# SpaceFleaEPS.net
KiCad netlist of a schematic drawn in EAGLE
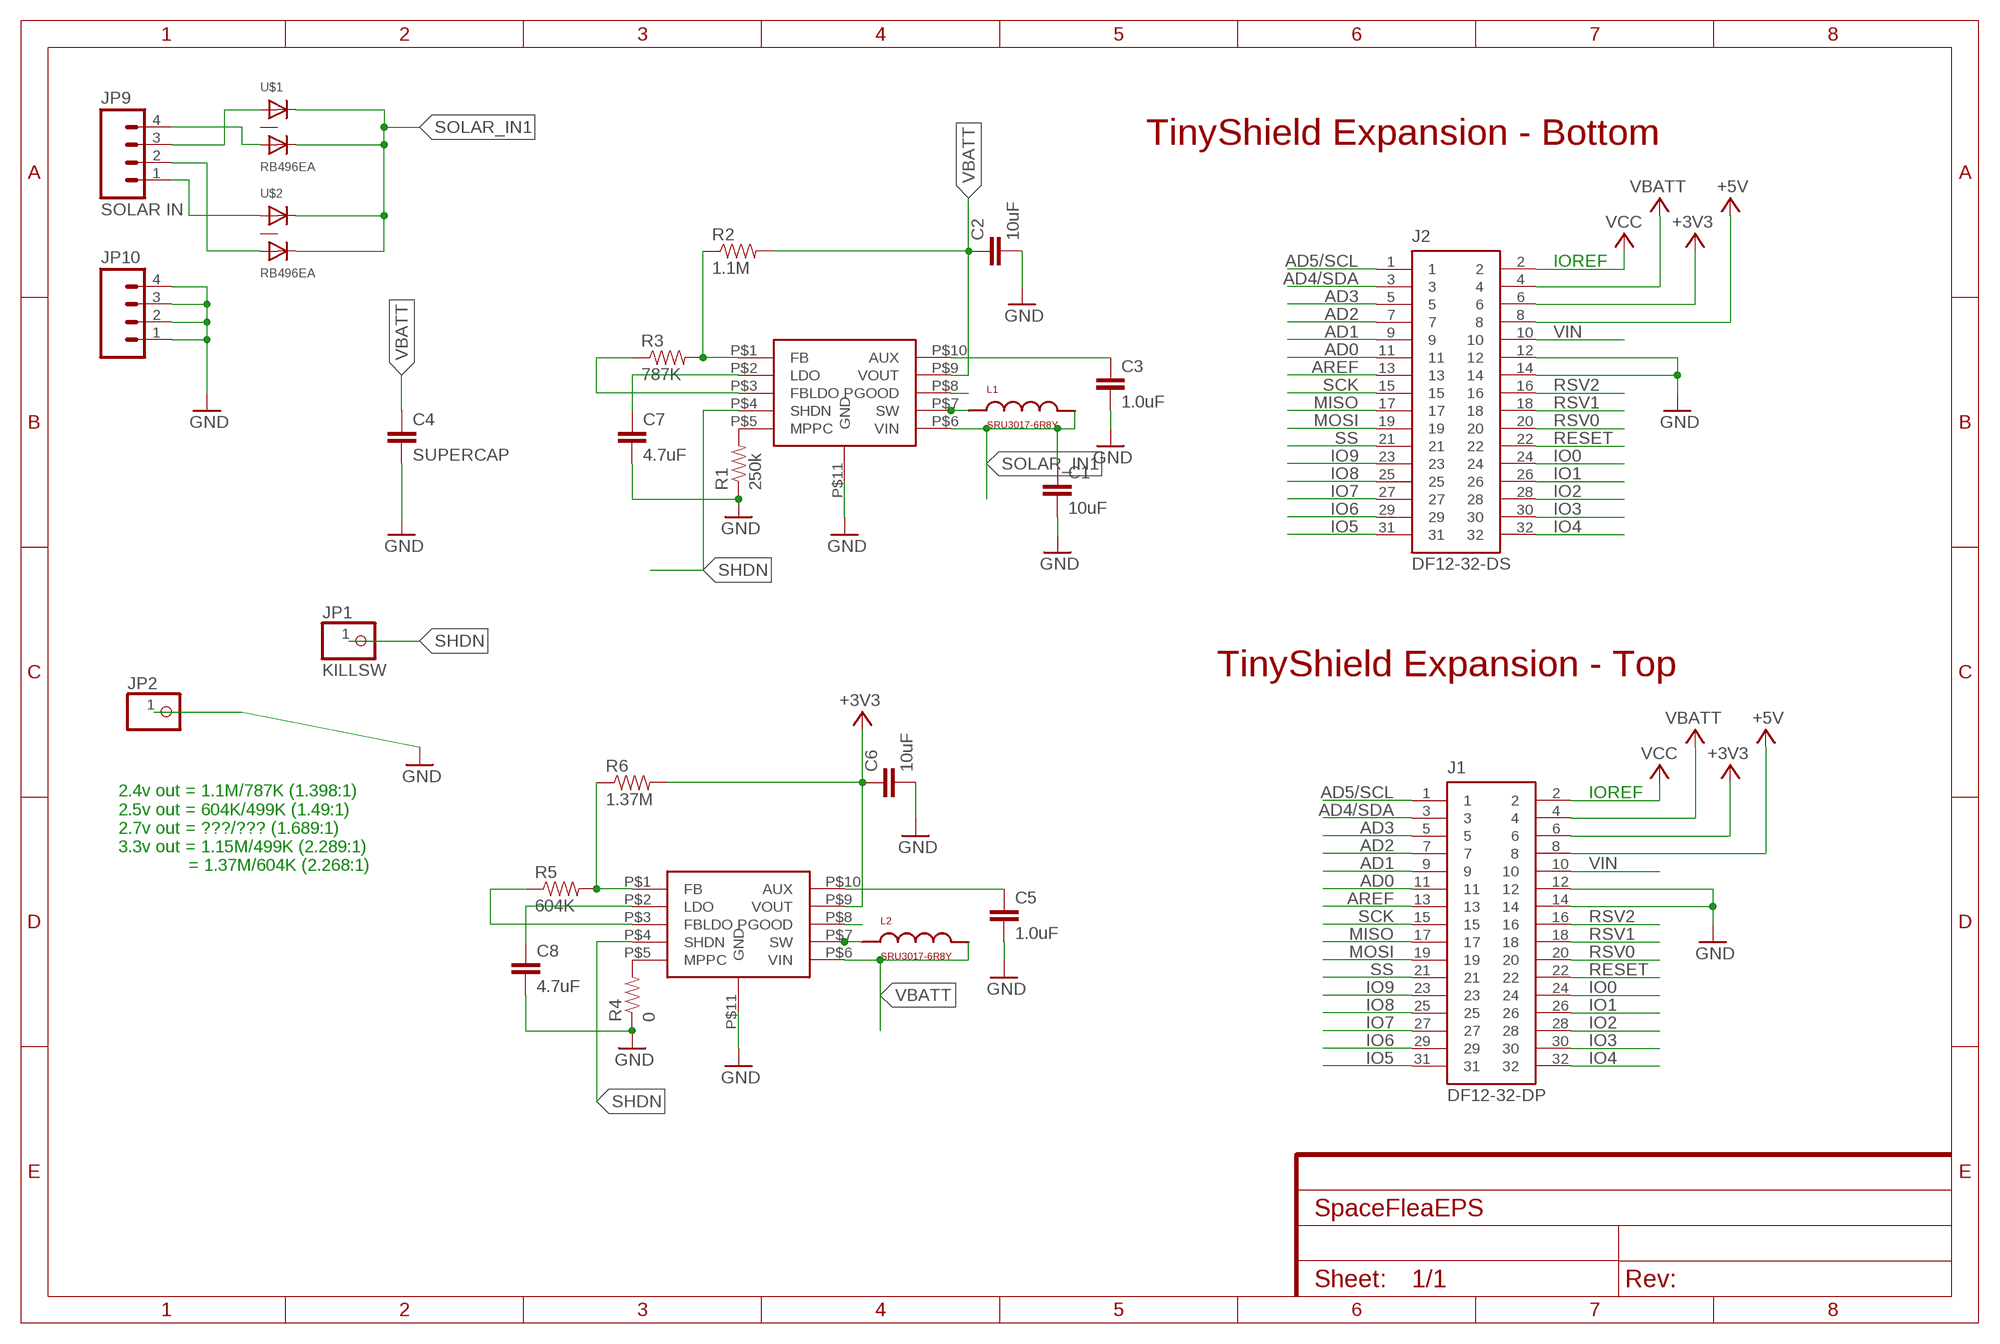
[diagram p0: schematic, sheet 1]

(export (version "E")
  (design (tool "Eeschema 10.0.6"))
  (components
    (comp (ref "C1")
      (value "10uF")
      (footprint "eagle-import:0805")
      (libsource (lib "eagle-import") (part "CAP0805"))
    )
    (comp (ref "C2")
      (value "10uF")
      (footprint "eagle-import:0805")
      (libsource (lib "eagle-import") (part "CAP0805"))
    )
    (comp (ref "C3")
      (value "1.0uF")
      (footprint "eagle-import:0603-CAP")
      (libsource (lib "eagle-import") (part "1.0UF-16V-10%(0603)"))
    )
    (comp (ref "C4")
      (value "SUPERCAP")
      (footprint "eagle-import:CAP-PTH-5MM")
      (libsource (lib "eagle-import") (part "CAPPTH1"))
    )
    (comp (ref "C5")
      (value "1.0uF")
      (footprint "eagle-import:0603-CAP")
      (libsource (lib "eagle-import") (part "1.0UF-16V-10%(0603)"))
    )
    (comp (ref "C6")
      (value "10uF")
      (footprint "eagle-import:0805")
      (libsource (lib "eagle-import") (part "CAP0805"))
    )
    (comp (ref "C7")
      (value "4.7uF")
      (footprint "eagle-import:0603-CAP")
      (libsource (lib "eagle-import") (part "CAP0603-CAP"))
    )
    (comp (ref "C8")
      (value "4.7uF")
      (footprint "eagle-import:0603-CAP")
      (libsource (lib "eagle-import") (part "CAP0603-CAP"))
    )
    (comp (ref "J1")
      (value "DF12-32-DP")
      (footprint "eagle-import:DF12-32-DP")
      (fields (field (name "PARTNO") "AS-ITM-00015") (field (name "PARTNO_1") "AS-ITM-00015"))
      (libsource (lib "eagle-import") (part "AS-ITM-00015"))
    )
    (comp (ref "J2")
      (value "DF12-32-DS")
      (footprint "eagle-import:DF12-32-DS")
      (fields (field (name "PARTNO") "AS-ITM-00012") (field (name "PARTNO_1") "AS-ITM-00012"))
      (libsource (lib "eagle-import") (part "AS-ITM-00012"))
    )
    (comp (ref "JP1")
      (value "KILLSW")
      (footprint "eagle-import:1X01_2MM")
      (libsource (lib "eagle-import") (part "HEADER-1X12MM"))
    )
    (comp (ref "JP2")
      (value "HEADER-1X12MM")
      (footprint "eagle-import:1X01_2MM")
      (libsource (lib "eagle-import") (part "HEADER-1X12MM"))
    )
    (comp (ref "JP9")
      (value "SOLAR IN")
      (footprint "eagle-import:1X04-1.27MM")
      (libsource (lib "eagle-import") (part "M041.27MM"))
    )
    (comp (ref "JP10")
      (value "M041.27MM")
      (footprint "eagle-import:1X04-1.27MM")
      (libsource (lib "eagle-import") (part "M041.27MM"))
    )
    (comp (ref "L1")
      (value "SRU3017-6R8Y")
      (footprint "eagle-import:SRU3017-6R8Y")
      (libsource (lib "eagle-import") (part "SRU3017-6R8Y"))
    )
    (comp (ref "L2")
      (value "SRU3017-6R8Y")
      (footprint "eagle-import:SRU3017-6R8Y")
      (libsource (lib "eagle-import") (part "SRU3017-6R8Y"))
    )
    (comp (ref "R1")
      (value "250k")
      (footprint "eagle-import:0402-RES")
      (libsource (lib "eagle-import") (part "RESISTOR0402-RES"))
    )
    (comp (ref "R2")
      (value "1.1M")
      (footprint "eagle-import:0402-RES")
      (libsource (lib "eagle-import") (part "RESISTOR0402-RES"))
    )
    (comp (ref "R3")
      (value "787K")
      (footprint "eagle-import:0402-RES")
      (libsource (lib "eagle-import") (part "RESISTOR0402-RES"))
    )
    (comp (ref "R4")
      (value "0")
      (footprint "eagle-import:0402-RES")
      (libsource (lib "eagle-import") (part "RESISTOR0402-RES"))
    )
    (comp (ref "R5")
      (value "604K")
      (footprint "eagle-import:0402-RES")
      (libsource (lib "eagle-import") (part "RESISTOR0402-RES"))
    )
    (comp (ref "R6")
      (value "1.37M")
      (footprint "eagle-import:0402-RES")
      (libsource (lib "eagle-import") (part "RESISTOR0402-RES"))
    )
    (comp (ref "U$1")
      (value "RB496EA")
      (footprint "eagle-import:SOT23-5")
      (libsource (lib "eagle-import") (part "RB496EA"))
    )
    (comp (ref "U$2")
      (value "RB496EA")
      (footprint "eagle-import:SOT23-5")
      (libsource (lib "eagle-import") (part "RB496EA"))
    )
    (comp (ref "U$3")
      (value "LTC3105_DFN")
      (footprint "eagle-import:LTC3105DFN")
      (libsource (lib "eagle-import") (part "LTC3105_DFN"))
    )
    (comp (ref "U$5")
      (value "LTC3105_DFN")
      (footprint "eagle-import:LTC3105DFN")
      (libsource (lib "eagle-import") (part "LTC3105_DFN"))
    )
  )
  (nets
    (net (code "1") (name "+3V3") (class "Default")
      (node (ref "C6") (pin "1") (pinfunction "1_1") (pintype "passive"))
      (node (ref "J1") (pin "6") (pinfunction "6_6") (pintype "bidirectional"))
      (node (ref "J2") (pin "6") (pinfunction "6_6") (pintype "bidirectional"))
      (node (ref "R6") (pin "2") (pinfunction "2_2") (pintype "passive"))
      (node (ref "U$3") (pin "P$9") (pinfunction "VOUT_P$9") (pintype "power_in"))
    )
    (net (code "2") (name "+5V") (class "Default")
      (node (ref "J1") (pin "8") (pinfunction "8_8") (pintype "bidirectional"))
      (node (ref "J2") (pin "8") (pinfunction "8_8") (pintype "bidirectional"))
    )
    (net (code "3") (name "/AD0") (class "Default")
      (node (ref "J1") (pin "11") (pinfunction "11_11") (pintype "bidirectional"))
      (node (ref "J2") (pin "11") (pinfunction "11_11") (pintype "bidirectional"))
    )
    (net (code "4") (name "/AD1") (class "Default")
      (node (ref "J1") (pin "9") (pinfunction "9_9") (pintype "bidirectional"))
      (node (ref "J2") (pin "9") (pinfunction "9_9") (pintype "bidirectional"))
    )
    (net (code "5") (name "/AD2") (class "Default")
      (node (ref "J1") (pin "7") (pinfunction "7_7") (pintype "bidirectional"))
      (node (ref "J2") (pin "7") (pinfunction "7_7") (pintype "bidirectional"))
    )
    (net (code "6") (name "/AD3") (class "Default")
      (node (ref "J1") (pin "5") (pinfunction "5_5") (pintype "bidirectional"))
      (node (ref "J2") (pin "5") (pinfunction "5_5") (pintype "bidirectional"))
    )
    (net (code "7") (name "/AD4{slash}SDA") (class "Default")
      (node (ref "J1") (pin "3") (pinfunction "3_3") (pintype "bidirectional"))
      (node (ref "J2") (pin "3") (pinfunction "3_3") (pintype "bidirectional"))
    )
    (net (code "8") (name "/AD5{slash}SCL") (class "Default")
      (node (ref "J1") (pin "1") (pinfunction "1_1") (pintype "bidirectional"))
      (node (ref "J2") (pin "1") (pinfunction "1_1") (pintype "bidirectional"))
    )
    (net (code "9") (name "/AREF") (class "Default")
      (node (ref "J1") (pin "13") (pinfunction "13_13") (pintype "bidirectional"))
      (node (ref "J2") (pin "13") (pinfunction "13_13") (pintype "bidirectional"))
    )
    (net (code "10") (name "/IO0") (class "Default")
      (node (ref "J1") (pin "24") (pinfunction "24_24") (pintype "bidirectional"))
      (node (ref "J2") (pin "24") (pinfunction "24_24") (pintype "bidirectional"))
    )
    (net (code "11") (name "/IO1") (class "Default")
      (node (ref "J1") (pin "26") (pinfunction "26_26") (pintype "bidirectional"))
      (node (ref "J2") (pin "26") (pinfunction "26_26") (pintype "bidirectional"))
    )
    (net (code "12") (name "/IO2") (class "Default")
      (node (ref "J1") (pin "28") (pinfunction "28_28") (pintype "bidirectional"))
      (node (ref "J2") (pin "28") (pinfunction "28_28") (pintype "bidirectional"))
    )
    (net (code "13") (name "/IO3") (class "Default")
      (node (ref "J1") (pin "30") (pinfunction "30_30") (pintype "bidirectional"))
      (node (ref "J2") (pin "30") (pinfunction "30_30") (pintype "bidirectional"))
    )
    (net (code "14") (name "/IO4") (class "Default")
      (node (ref "J1") (pin "32") (pinfunction "32_32") (pintype "bidirectional"))
      (node (ref "J2") (pin "32") (pinfunction "32_32") (pintype "bidirectional"))
    )
    (net (code "15") (name "/IO5") (class "Default")
      (node (ref "J1") (pin "31") (pinfunction "31_31") (pintype "bidirectional"))
      (node (ref "J2") (pin "31") (pinfunction "31_31") (pintype "bidirectional"))
    )
    (net (code "16") (name "/IO6") (class "Default")
      (node (ref "J1") (pin "29") (pinfunction "29_29") (pintype "bidirectional"))
      (node (ref "J2") (pin "29") (pinfunction "29_29") (pintype "bidirectional"))
    )
    (net (code "17") (name "/IO7") (class "Default")
      (node (ref "J1") (pin "27") (pinfunction "27_27") (pintype "bidirectional"))
      (node (ref "J2") (pin "27") (pinfunction "27_27") (pintype "bidirectional"))
    )
    (net (code "18") (name "/IO8") (class "Default")
      (node (ref "J1") (pin "25") (pinfunction "25_25") (pintype "bidirectional"))
      (node (ref "J2") (pin "25") (pinfunction "25_25") (pintype "bidirectional"))
    )
    (net (code "19") (name "/IO9") (class "Default")
      (node (ref "J1") (pin "23") (pinfunction "23_23") (pintype "bidirectional"))
      (node (ref "J2") (pin "23") (pinfunction "23_23") (pintype "bidirectional"))
    )
    (net (code "20") (name "/MISO") (class "Default")
      (node (ref "J1") (pin "17") (pinfunction "17_17") (pintype "bidirectional"))
      (node (ref "J2") (pin "17") (pinfunction "17_17") (pintype "bidirectional"))
    )
    (net (code "21") (name "/MOSI") (class "Default")
      (node (ref "J1") (pin "19") (pinfunction "19_19") (pintype "bidirectional"))
      (node (ref "J2") (pin "19") (pinfunction "19_19") (pintype "bidirectional"))
    )
    (net (code "22") (name "/RESET") (class "Default")
      (node (ref "J1") (pin "22") (pinfunction "22_22") (pintype "bidirectional"))
      (node (ref "J2") (pin "22") (pinfunction "22_22") (pintype "bidirectional"))
    )
    (net (code "23") (name "/RSV0") (class "Default")
      (node (ref "J1") (pin "20") (pinfunction "20_20") (pintype "bidirectional"))
      (node (ref "J2") (pin "20") (pinfunction "20_20") (pintype "bidirectional"))
    )
    (net (code "24") (name "/RSV1") (class "Default")
      (node (ref "J1") (pin "18") (pinfunction "18_18") (pintype "bidirectional"))
      (node (ref "J2") (pin "18") (pinfunction "18_18") (pintype "bidirectional"))
    )
    (net (code "25") (name "/RSV2") (class "Default")
      (node (ref "J1") (pin "16") (pinfunction "16_16") (pintype "bidirectional"))
      (node (ref "J2") (pin "16") (pinfunction "16_16") (pintype "bidirectional"))
    )
    (net (code "26") (name "/SCK") (class "Default")
      (node (ref "J1") (pin "15") (pinfunction "15_15") (pintype "bidirectional"))
      (node (ref "J2") (pin "15") (pinfunction "15_15") (pintype "bidirectional"))
    )
    (net (code "27") (name "/SS") (class "Default")
      (node (ref "J1") (pin "21") (pinfunction "21_21") (pintype "bidirectional"))
      (node (ref "J2") (pin "21") (pinfunction "21_21") (pintype "bidirectional"))
    )
    (net (code "28") (name "/VIN") (class "Default")
      (node (ref "J1") (pin "10") (pinfunction "10_10") (pintype "bidirectional"))
      (node (ref "J2") (pin "10") (pinfunction "10_10") (pintype "bidirectional"))
    )
    (net (code "29") (name "GND") (class "Default")
      (node (ref "C1") (pin "2") (pinfunction "2_2") (pintype "passive"))
      (node (ref "C2") (pin "2") (pinfunction "2_2") (pintype "passive"))
      (node (ref "C3") (pin "2") (pinfunction "2_2") (pintype "passive"))
      (node (ref "C4") (pin "2") (pinfunction "2_2") (pintype "passive"))
      (node (ref "C5") (pin "2") (pinfunction "2_2") (pintype "passive"))
      (node (ref "C6") (pin "2") (pinfunction "2_2") (pintype "passive"))
      (node (ref "C7") (pin "2") (pinfunction "2_2") (pintype "passive"))
      (node (ref "C8") (pin "2") (pinfunction "2_2") (pintype "passive"))
      (node (ref "J1") (pin "12") (pinfunction "12_12") (pintype "bidirectional"))
      (node (ref "J1") (pin "14") (pinfunction "14_14") (pintype "bidirectional"))
      (node (ref "J2") (pin "12") (pinfunction "12_12") (pintype "bidirectional"))
      (node (ref "J2") (pin "14") (pinfunction "14_14") (pintype "bidirectional"))
      (node (ref "JP10") (pin "1") (pinfunction "1_1") (pintype "passive"))
      (node (ref "JP10") (pin "2") (pinfunction "2_2") (pintype "passive"))
      (node (ref "JP10") (pin "3") (pinfunction "3_3") (pintype "passive"))
      (node (ref "JP10") (pin "4") (pinfunction "4_4") (pintype "passive"))
      (node (ref "JP2") (pin "1") (pinfunction "1_1") (pintype "passive"))
      (node (ref "R1") (pin "1") (pinfunction "1_1") (pintype "passive"))
      (node (ref "R3") (pin "1") (pinfunction "1_1") (pintype "passive"))
      (node (ref "R4") (pin "1") (pinfunction "1_1") (pintype "passive"))
      (node (ref "R5") (pin "1") (pinfunction "1_1") (pintype "passive"))
      (node (ref "U$3") (pin "P$11") (pinfunction "GND_P$11") (pintype "power_in"))
      (node (ref "U$3") (pin "P$3") (pinfunction "FBLDO_P$3") (pintype "power_in"))
      (node (ref "U$5") (pin "P$11") (pinfunction "GND_P$11") (pintype "power_in"))
      (node (ref "U$5") (pin "P$3") (pinfunction "FBLDO_P$3") (pintype "power_in"))
    )
    (net (code "30") (name "Net-(JP9-Pad1)") (class "Default")
      (node (ref "JP9") (pin "1") (pinfunction "1_1") (pintype "passive"))
      (node (ref "U$2") (pin "1") (pinfunction "1_1") (pintype "passive"))
    )
    (net (code "31") (name "Net-(JP9-Pad2)") (class "Default")
      (node (ref "JP9") (pin "2") (pinfunction "2_2") (pintype "passive"))
      (node (ref "U$2") (pin "3") (pinfunction "3_3") (pintype "passive"))
    )
    (net (code "32") (name "Net-(JP9-Pad3)") (class "Default")
      (node (ref "JP9") (pin "3") (pinfunction "3_3") (pintype "passive"))
      (node (ref "U$1") (pin "1") (pinfunction "1_1") (pintype "passive"))
    )
    (net (code "33") (name "Net-(JP9-Pad4)") (class "Default")
      (node (ref "JP9") (pin "4") (pinfunction "4_4") (pintype "passive"))
      (node (ref "U$1") (pin "3") (pinfunction "3_3") (pintype "passive"))
    )
    (net (code "34") (name "Net-(U$3-AUX)") (class "Default")
      (node (ref "C5") (pin "1") (pinfunction "1_1") (pintype "passive"))
      (node (ref "U$3") (pin "P$10") (pinfunction "AUX_P$10") (pintype "power_in"))
    )
    (net (code "35") (name "Net-(U$3-FB)") (class "Default")
      (node (ref "R5") (pin "2") (pinfunction "2_2") (pintype "passive"))
      (node (ref "R6") (pin "1") (pinfunction "1_1") (pintype "passive"))
      (node (ref "U$3") (pin "P$1") (pinfunction "FB_P$1") (pintype "power_in"))
    )
    (net (code "36") (name "Net-(U$3-LDO)") (class "Default")
      (node (ref "C8") (pin "1") (pinfunction "1_1") (pintype "passive"))
      (node (ref "U$3") (pin "P$2") (pinfunction "LDO_P$2") (pintype "power_in"))
    )
    (net (code "37") (name "Net-(U$3-MPPC)") (class "Default")
      (node (ref "R4") (pin "2") (pinfunction "2_2") (pintype "passive"))
      (node (ref "U$3") (pin "P$5") (pinfunction "MPPC_P$5") (pintype "power_in"))
    )
    (net (code "38") (name "Net-(U$3-SW)") (class "Default")
      (node (ref "L2") (pin "P$1") (pinfunction "P$1_P$1") (pintype "passive"))
      (node (ref "U$3") (pin "P$7") (pinfunction "SW_P$7") (pintype "power_in"))
    )
    (net (code "39") (name "Net-(U$5-AUX)") (class "Default")
      (node (ref "C3") (pin "1") (pinfunction "1_1") (pintype "passive"))
      (node (ref "U$5") (pin "P$10") (pinfunction "AUX_P$10") (pintype "power_in"))
    )
    (net (code "40") (name "Net-(U$5-FB)") (class "Default")
      (node (ref "R2") (pin "1") (pinfunction "1_1") (pintype "passive"))
      (node (ref "R3") (pin "2") (pinfunction "2_2") (pintype "passive"))
      (node (ref "U$5") (pin "P$1") (pinfunction "FB_P$1") (pintype "power_in"))
    )
    (net (code "41") (name "Net-(U$5-LDO)") (class "Default")
      (node (ref "C7") (pin "1") (pinfunction "1_1") (pintype "passive"))
      (node (ref "U$5") (pin "P$2") (pinfunction "LDO_P$2") (pintype "power_in"))
    )
    (net (code "42") (name "Net-(U$5-MPPC)") (class "Default")
      (node (ref "R1") (pin "2") (pinfunction "2_2") (pintype "passive"))
      (node (ref "U$5") (pin "P$5") (pinfunction "MPPC_P$5") (pintype "power_in"))
    )
    (net (code "43") (name "Net-(U$5-SW)") (class "Default")
      (node (ref "L1") (pin "P$1") (pinfunction "P$1_P$1") (pintype "passive"))
      (node (ref "U$5") (pin "P$7") (pinfunction "SW_P$7") (pintype "power_in"))
    )
    (net (code "44") (name "SHDN") (class "Default")
      (node (ref "JP1") (pin "1") (pinfunction "1_1") (pintype "passive"))
      (node (ref "U$3") (pin "P$4") (pinfunction "SHDN_P$4") (pintype "bidirectional"))
      (node (ref "U$5") (pin "P$4") (pinfunction "SHDN_P$4") (pintype "bidirectional"))
    )
    (net (code "45") (name "SOLAR_IN1") (class "Default")
      (node (ref "C1") (pin "1") (pinfunction "1_1") (pintype "passive"))
      (node (ref "L1") (pin "P$2") (pinfunction "P$2_P$2") (pintype "passive"))
      (node (ref "U$1") (pin "4") (pinfunction "4_4") (pintype "passive"))
      (node (ref "U$1") (pin "5") (pinfunction "5_5") (pintype "passive"))
      (node (ref "U$2") (pin "4") (pinfunction "4_4") (pintype "passive"))
      (node (ref "U$2") (pin "5") (pinfunction "5_5") (pintype "passive"))
      (node (ref "U$5") (pin "P$6") (pinfunction "VIN_P$6") (pintype "power_in"))
    )
    (net (code "46") (name "VBATT") (class "Default")
      (node (ref "C2") (pin "1") (pinfunction "1_1") (pintype "passive"))
      (node (ref "C4") (pin "1") (pinfunction "1_1") (pintype "passive"))
      (node (ref "J1") (pin "4") (pinfunction "4_4") (pintype "bidirectional"))
      (node (ref "J2") (pin "4") (pinfunction "4_4") (pintype "bidirectional"))
      (node (ref "L2") (pin "P$2") (pinfunction "P$2_P$2") (pintype "passive"))
      (node (ref "R2") (pin "2") (pinfunction "2_2") (pintype "passive"))
      (node (ref "U$3") (pin "P$6") (pinfunction "VIN_P$6") (pintype "power_in"))
      (node (ref "U$5") (pin "P$9") (pinfunction "VOUT_P$9") (pintype "power_in"))
    )
    (net (code "47") (name "VCC") (class "Default")
      (node (ref "J1") (pin "2") (pinfunction "2_2") (pintype "bidirectional"))
      (node (ref "J2") (pin "2") (pinfunction "2_2") (pintype "bidirectional"))
    )
    (net (code "48") (name "unconnected-(U$1-Pad2)") (class "Default")
      (node (ref "U$1") (pin "2") (pinfunction "2_2") (pintype "no_connect"))
    )
    (net (code "49") (name "unconnected-(U$2-Pad2)") (class "Default")
      (node (ref "U$2") (pin "2") (pinfunction "2_2") (pintype "no_connect"))
    )
    (net (code "50") (name "unconnected-(U$3-PGOOD-PadP$8)") (class "Default")
      (node (ref "U$3") (pin "P$8") (pinfunction "PGOOD_P$8") (pintype "bidirectional"))
    )
    (net (code "51") (name "unconnected-(U$5-PGOOD-PadP$8)") (class "Default")
      (node (ref "U$5") (pin "P$8") (pinfunction "PGOOD_P$8") (pintype "bidirectional"))
    )
  )
)
